# axe_tomb.net
KiCad netlist of a schematic drawn in EAGLE
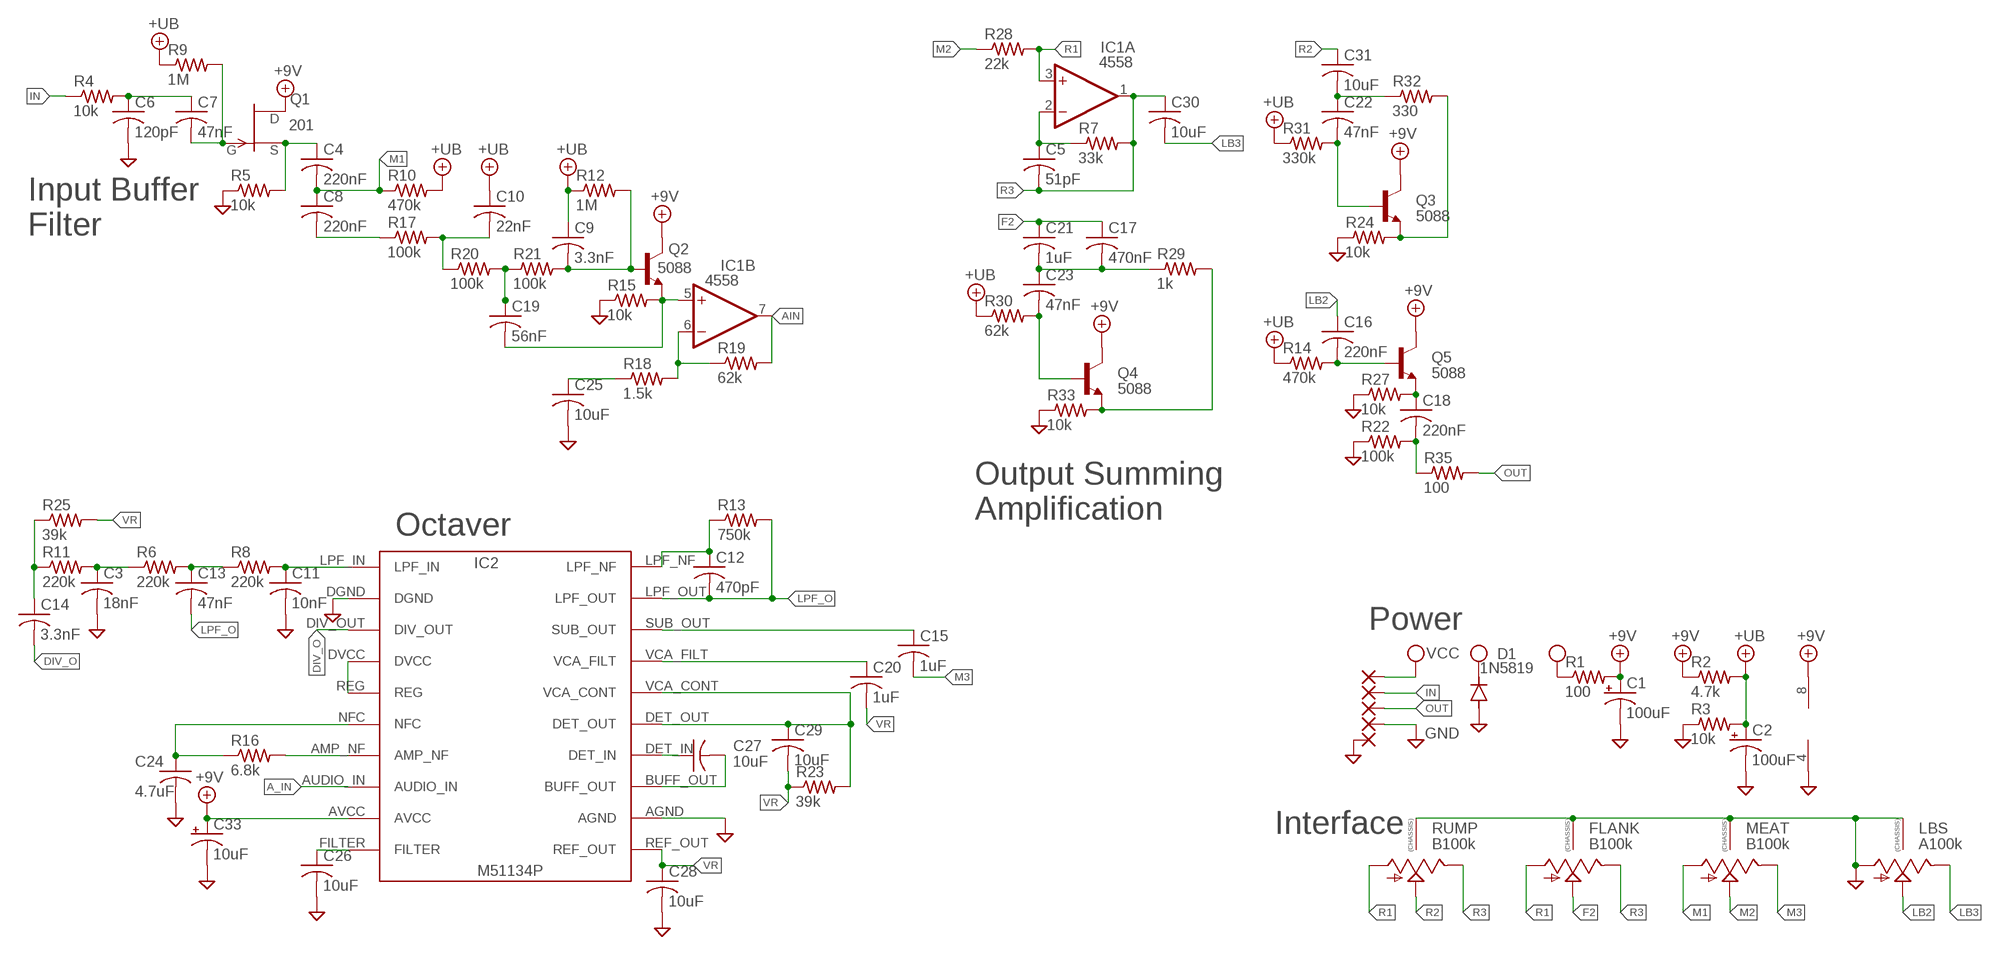
[diagram p0: schematic, sheet 1]

(export (version "E")
  (design (tool "Eeschema 10.0.6"))
  (components
    (comp (ref "C1")
      (value "100uF")
      (footprint "eagle-import:CPOL-RADIAL-2.5MM-6.5MM")
      (libsource (lib "eagle-import") (part "100UF-POLAR-RADIAL-2.5MM-25V-20%"))
    )
    (comp (ref "C2")
      (value "100uF")
      (footprint "eagle-import:CPOL-RADIAL-2.5MM-6.5MM")
      (libsource (lib "eagle-import") (part "100UF-POLAR-RADIAL-2.5MM-25V-20%"))
    )
    (comp (ref "C3")
      (value "18nF")
      (footprint "eagle-import:C0603")
      (libsource (lib "eagle-import") (part "C-USC0603"))
    )
    (comp (ref "C4")
      (value "220nF")
      (footprint "eagle-import:C0603")
      (libsource (lib "eagle-import") (part "C-USC0603"))
    )
    (comp (ref "C5")
      (value "51pF")
      (footprint "eagle-import:C0603")
      (libsource (lib "eagle-import") (part "C-USC0603"))
    )
    (comp (ref "C6")
      (value "120pF")
      (footprint "eagle-import:C0603")
      (libsource (lib "eagle-import") (part "C-USC0603"))
    )
    (comp (ref "C7")
      (value "47nF")
      (footprint "eagle-import:C0603")
      (libsource (lib "eagle-import") (part "C-USC0603"))
    )
    (comp (ref "C8")
      (value "220nF")
      (footprint "eagle-import:C0603")
      (libsource (lib "eagle-import") (part "C-USC0603"))
    )
    (comp (ref "C9")
      (value "3.3nF")
      (footprint "eagle-import:C0603")
      (libsource (lib "eagle-import") (part "C-USC0603"))
    )
    (comp (ref "C10")
      (value "22nF")
      (footprint "eagle-import:C0603")
      (libsource (lib "eagle-import") (part "C-USC0603"))
    )
    (comp (ref "C11")
      (value "10nF")
      (footprint "eagle-import:C0603")
      (libsource (lib "eagle-import") (part "C-USC0603"))
    )
    (comp (ref "C12")
      (value "470pF")
      (footprint "eagle-import:C0603")
      (libsource (lib "eagle-import") (part "C-USC0603"))
    )
    (comp (ref "C13")
      (value "47nF")
      (footprint "eagle-import:C0603")
      (libsource (lib "eagle-import") (part "C-USC0603"))
    )
    (comp (ref "C14")
      (value "3.3nF")
      (footprint "eagle-import:C0603")
      (libsource (lib "eagle-import") (part "C-USC0603"))
    )
    (comp (ref "C15")
      (value "1uF")
      (footprint "eagle-import:C0603")
      (libsource (lib "eagle-import") (part "C-USC0603"))
    )
    (comp (ref "C16")
      (value "220nF")
      (footprint "eagle-import:C0603")
      (libsource (lib "eagle-import") (part "C-USC0603"))
    )
    (comp (ref "C17")
      (value "470nF")
      (footprint "eagle-import:C0603")
      (libsource (lib "eagle-import") (part "C-USC0603"))
    )
    (comp (ref "C18")
      (value "220nF")
      (footprint "eagle-import:C0603")
      (libsource (lib "eagle-import") (part "C-USC0603"))
    )
    (comp (ref "C19")
      (value "56nF")
      (footprint "eagle-import:C0603")
      (libsource (lib "eagle-import") (part "C-USC0603"))
    )
    (comp (ref "C20")
      (value "1uF")
      (footprint "eagle-import:C0603")
      (libsource (lib "eagle-import") (part "C-USC0603"))
    )
    (comp (ref "C21")
      (value "1uF")
      (footprint "eagle-import:C0603")
      (libsource (lib "eagle-import") (part "C-USC0603"))
    )
    (comp (ref "C22")
      (value "47nF")
      (footprint "eagle-import:C0603")
      (libsource (lib "eagle-import") (part "C-USC0603"))
    )
    (comp (ref "C23")
      (value "47nF")
      (footprint "eagle-import:C0603")
      (libsource (lib "eagle-import") (part "C-USC0603"))
    )
    (comp (ref "C24")
      (value "4.7uF")
      (footprint "eagle-import:C1206")
      (libsource (lib "eagle-import") (part "C-USC1206"))
    )
    (comp (ref "C25")
      (value "10uF")
      (footprint "eagle-import:C1206")
      (libsource (lib "eagle-import") (part "C-USC1206"))
    )
    (comp (ref "C26")
      (value "10uF")
      (footprint "eagle-import:C1206")
      (libsource (lib "eagle-import") (part "C-USC1206"))
    )
    (comp (ref "C27")
      (value "10uF")
      (footprint "eagle-import:C1206")
      (libsource (lib "eagle-import") (part "C-USC1206"))
    )
    (comp (ref "C28")
      (value "10uF")
      (footprint "eagle-import:C1206")
      (libsource (lib "eagle-import") (part "C-USC1206"))
    )
    (comp (ref "C29")
      (value "10uF")
      (footprint "eagle-import:C1206")
      (libsource (lib "eagle-import") (part "C-USC1206"))
    )
    (comp (ref "C30")
      (value "10uF")
      (footprint "eagle-import:C1206")
      (libsource (lib "eagle-import") (part "C-USC1206"))
    )
    (comp (ref "C31")
      (value "10uF")
      (footprint "eagle-import:C1206")
      (libsource (lib "eagle-import") (part "C-USC1206"))
    )
    (comp (ref "C33")
      (value "10uF")
      (footprint "eagle-import:CAPMP3216X180N")
      (libsource (lib "eagle-import") (part "C-POL-USTANTALUM-1206(3216-METRIC)_"))
    )
    (comp (ref "D1")
      (value "1N5819")
      (footprint "eagle-import:SOD123")
      (libsource (lib "eagle-import") (part "DIODE-SOD123"))
    )
    (comp (ref "FLANK")
      (value "B100k")
      (footprint "eagle-import:9MM_SNAP-IN_POT")
      (libsource (lib "eagle-import") (part "9MM_SNAP-IN_POT_CHASSIS"))
    )
    (comp (ref "IC1")
      (value "4558")
      (footprint "eagle-import:SO08")
      (libsource (lib "eagle-import") (part "4558DLM"))
    )
    (comp (ref "IC2")
      (value "M51134P")
      (footprint "eagle-import:M51134P")
      (libsource (lib "eagle-import") (part "M51134P"))
    )
    (comp (ref "LBS")
      (value "A100k")
      (footprint "eagle-import:9MM_SNAP-IN_POT")
      (libsource (lib "eagle-import") (part "9MM_SNAP-IN_POT_CHASSIS"))
    )
    (comp (ref "MEAT")
      (value "B100k")
      (footprint "eagle-import:9MM_SNAP-IN_POT")
      (libsource (lib "eagle-import") (part "9MM_SNAP-IN_POT_CHASSIS"))
    )
    (comp (ref "PAD1")
      (value "1,6/0,8")
      (footprint "eagle-import:1,6_0,8")
      (libsource (lib "eagle-import") (part "1,6/0,8"))
    )
    (comp (ref "PAD2")
      (value "1,6/0,8")
      (footprint "eagle-import:1,6_0,8")
      (libsource (lib "eagle-import") (part "1,6/0,8"))
    )
    (comp (ref "PAD3")
      (value "1,6/0,8")
      (footprint "eagle-import:1,6_0,8")
      (libsource (lib "eagle-import") (part "1,6/0,8"))
    )
    (comp (ref "PAD4")
      (value "1,6/0,8")
      (footprint "eagle-import:1,6_0,8")
      (libsource (lib "eagle-import") (part "1,6/0,8"))
    )
    (comp (ref "PAD5")
      (value "1,6/0,8")
      (footprint "eagle-import:1,6_0,8")
      (libsource (lib "eagle-import") (part "1,6/0,8"))
    )
    (comp (ref "Q1")
      (value "201")
      (footprint "eagle-import:SOT23")
      (libsource (lib "eagle-import") (part "?20SST1"))
    )
    (comp (ref "Q2")
      (value "5088")
      (footprint "eagle-import:SOT23")
      (libsource (lib "eagle-import") (part "TRANSISTOR_NPNMMBT5088"))
    )
    (comp (ref "Q3")
      (value "5088")
      (footprint "eagle-import:SOT23")
      (libsource (lib "eagle-import") (part "TRANSISTOR_NPNMMBT5088"))
    )
    (comp (ref "Q4")
      (value "5088")
      (footprint "eagle-import:SOT23")
      (libsource (lib "eagle-import") (part "TRANSISTOR_NPNMMBT5088"))
    )
    (comp (ref "Q5")
      (value "5088")
      (footprint "eagle-import:SOT23")
      (libsource (lib "eagle-import") (part "TRANSISTOR_NPNMMBT5088"))
    )
    (comp (ref "R1")
      (value "100")
      (footprint "eagle-import:R0805")
      (libsource (lib "eagle-import") (part "adafruit_420_R-US_R0805"))
    )
    (comp (ref "R2")
      (value "4.7k")
      (footprint "eagle-import:R0603")
      (libsource (lib "eagle-import") (part "R-US_R0603"))
    )
    (comp (ref "R3")
      (value "10k")
      (footprint "eagle-import:R0603")
      (libsource (lib "eagle-import") (part "R-US_R0603"))
    )
    (comp (ref "R4")
      (value "10k")
      (footprint "eagle-import:R0603")
      (libsource (lib "eagle-import") (part "adafruit_420_R-US_R0603"))
    )
    (comp (ref "R5")
      (value "10k")
      (footprint "eagle-import:R0603")
      (libsource (lib "eagle-import") (part "adafruit_420_R-US_R0603"))
    )
    (comp (ref "R6")
      (value "220k")
      (footprint "eagle-import:R0603")
      (libsource (lib "eagle-import") (part "adafruit_420_R-US_R0603"))
    )
    (comp (ref "R7")
      (value "33k")
      (footprint "eagle-import:R0603")
      (libsource (lib "eagle-import") (part "adafruit_420_R-US_R0603"))
    )
    (comp (ref "R8")
      (value "220k")
      (footprint "eagle-import:R0603")
      (libsource (lib "eagle-import") (part "adafruit_420_R-US_R0603"))
    )
    (comp (ref "R9")
      (value "1M")
      (footprint "eagle-import:R0603")
      (libsource (lib "eagle-import") (part "adafruit_420_R-US_R0603"))
    )
    (comp (ref "R10")
      (value "470k")
      (footprint "eagle-import:R0603")
      (libsource (lib "eagle-import") (part "adafruit_420_R-US_R0603"))
    )
    (comp (ref "R11")
      (value "220k")
      (footprint "eagle-import:R0603")
      (libsource (lib "eagle-import") (part "adafruit_420_R-US_R0603"))
    )
    (comp (ref "R12")
      (value "1M")
      (footprint "eagle-import:R0603")
      (libsource (lib "eagle-import") (part "adafruit_420_R-US_R0603"))
    )
    (comp (ref "R13")
      (value "750k")
      (footprint "eagle-import:R0603")
      (libsource (lib "eagle-import") (part "adafruit_420_R-US_R0603"))
    )
    (comp (ref "R14")
      (value "470k")
      (footprint "eagle-import:R0603")
      (libsource (lib "eagle-import") (part "adafruit_420_R-US_R0603"))
    )
    (comp (ref "R15")
      (value "10k")
      (footprint "eagle-import:R0603")
      (libsource (lib "eagle-import") (part "adafruit_420_R-US_R0603"))
    )
    (comp (ref "R16")
      (value "6.8k")
      (footprint "eagle-import:R0603")
      (libsource (lib "eagle-import") (part "adafruit_420_R-US_R0603"))
    )
    (comp (ref "R17")
      (value "100k")
      (footprint "eagle-import:R0603")
      (libsource (lib "eagle-import") (part "adafruit_420_R-US_R0603"))
    )
    (comp (ref "R18")
      (value "1.5k")
      (footprint "eagle-import:R0603")
      (libsource (lib "eagle-import") (part "adafruit_420_R-US_R0603"))
    )
    (comp (ref "R19")
      (value "62k")
      (footprint "eagle-import:R0603")
      (libsource (lib "eagle-import") (part "adafruit_420_R-US_R0603"))
    )
    (comp (ref "R20")
      (value "100k")
      (footprint "eagle-import:R0603")
      (libsource (lib "eagle-import") (part "adafruit_420_R-US_R0603"))
    )
    (comp (ref "R21")
      (value "100k")
      (footprint "eagle-import:R0603")
      (libsource (lib "eagle-import") (part "adafruit_420_R-US_R0603"))
    )
    (comp (ref "R22")
      (value "100k")
      (footprint "eagle-import:R0603")
      (libsource (lib "eagle-import") (part "adafruit_420_R-US_R0603"))
    )
    (comp (ref "R23")
      (value "39k")
      (footprint "eagle-import:R0603")
      (libsource (lib "eagle-import") (part "adafruit_420_R-US_R0603"))
    )
    (comp (ref "R24")
      (value "10k")
      (footprint "eagle-import:R0603")
      (libsource (lib "eagle-import") (part "adafruit_420_R-US_R0603"))
    )
    (comp (ref "R25")
      (value "39k")
      (footprint "eagle-import:R0603")
      (libsource (lib "eagle-import") (part "adafruit_420_R-US_R0603"))
    )
    (comp (ref "R27")
      (value "10k")
      (footprint "eagle-import:R0603")
      (libsource (lib "eagle-import") (part "adafruit_420_R-US_R0603"))
    )
    (comp (ref "R28")
      (value "22k")
      (footprint "eagle-import:R0603")
      (libsource (lib "eagle-import") (part "adafruit_420_R-US_R0603"))
    )
    (comp (ref "R29")
      (value "1k")
      (footprint "eagle-import:R0603")
      (libsource (lib "eagle-import") (part "adafruit_420_R-US_R0603"))
    )
    (comp (ref "R30")
      (value "62k")
      (footprint "eagle-import:R0603")
      (libsource (lib "eagle-import") (part "adafruit_420_R-US_R0603"))
    )
    (comp (ref "R31")
      (value "330k")
      (footprint "eagle-import:R0603")
      (libsource (lib "eagle-import") (part "adafruit_420_R-US_R0603"))
    )
    (comp (ref "R32")
      (value "330")
      (footprint "eagle-import:R0603")
      (libsource (lib "eagle-import") (part "adafruit_420_R-US_R0603"))
    )
    (comp (ref "R33")
      (value "10k")
      (footprint "eagle-import:R0603")
      (libsource (lib "eagle-import") (part "adafruit_420_R-US_R0603"))
    )
    (comp (ref "R35")
      (value "100")
      (footprint "eagle-import:R0603")
      (libsource (lib "eagle-import") (part "adafruit_420_R-US_R0603"))
    )
    (comp (ref "RUMP")
      (value "B100k")
      (footprint "eagle-import:9MM_SNAP-IN_POT")
      (libsource (lib "eagle-import") (part "9MM_SNAP-IN_POT_CHASSIS"))
    )
  )
  (nets
    (net (code "1") (name "+9V") (class "Default")
      (node (ref "C1") (pin "1") (pinfunction "+_1") (pintype "passive"))
      (node (ref "C33") (pin "1") (pinfunction "+_1") (pintype "passive"))
      (node (ref "IC1") (pin "8") (pinfunction "V+_8") (pintype "power_in"))
      (node (ref "IC2") (pin "AVCC") (pinfunction "AVCC_AVCC") (pintype "bidirectional"))
      (node (ref "Q1") (pin "1") (pinfunction "D_1") (pintype "passive"))
      (node (ref "Q2") (pin "3") (pinfunction "C_3") (pintype "passive"))
      (node (ref "Q3") (pin "3") (pinfunction "C_3") (pintype "passive"))
      (node (ref "Q4") (pin "3") (pinfunction "C_3") (pintype "passive"))
      (node (ref "Q5") (pin "3") (pinfunction "C_3") (pintype "passive"))
      (node (ref "R1") (pin "2") (pinfunction "2_2") (pintype "passive"))
      (node (ref "R2") (pin "1") (pinfunction "1_1") (pintype "passive"))
    )
    (net (code "2") (name "+UB") (class "Default")
      (node (ref "C10") (pin "1") (pinfunction "1_1") (pintype "passive"))
      (node (ref "C2") (pin "1") (pinfunction "+_1") (pintype "passive"))
      (node (ref "C9") (pin "1") (pinfunction "1_1") (pintype "passive"))
      (node (ref "R10") (pin "2") (pinfunction "2_2") (pintype "passive"))
      (node (ref "R12") (pin "1") (pinfunction "1_1") (pintype "passive"))
      (node (ref "R14") (pin "1") (pinfunction "1_1") (pintype "passive"))
      (node (ref "R2") (pin "2") (pinfunction "2_2") (pintype "passive"))
      (node (ref "R3") (pin "2") (pinfunction "2_2") (pintype "passive"))
      (node (ref "R30") (pin "1") (pinfunction "1_1") (pintype "passive"))
      (node (ref "R31") (pin "1") (pinfunction "1_1") (pintype "passive"))
      (node (ref "R9") (pin "1") (pinfunction "1_1") (pintype "passive"))
    )
    (net (code "3") (name "AIN") (class "Default")
      (node (ref "IC1") (pin "7") (pinfunction "OUT_7") (pintype "output"))
      (node (ref "R19") (pin "2") (pinfunction "2_2") (pintype "passive"))
    )
    (net (code "4") (name "A_IN") (class "Default")
      (node (ref "IC2") (pin "AUDIO_IN") (pinfunction "AUDIO_IN_AUDIO_IN") (pintype "bidirectional"))
    )
    (net (code "5") (name "DIV_O") (class "Default")
      (node (ref "C14") (pin "2") (pinfunction "2_2") (pintype "passive"))
      (node (ref "IC2") (pin "DIV_OUT") (pinfunction "DIV_OUT_DIV_OUT") (pintype "bidirectional"))
    )
    (net (code "6") (name "F2") (class "Default")
      (node (ref "C17") (pin "1") (pinfunction "1_1") (pintype "passive"))
      (node (ref "C21") (pin "1") (pinfunction "1_1") (pintype "passive"))
      (node (ref "FLANK") (pin "2") (pinfunction "S_2") (pintype "passive"))
    )
    (net (code "7") (name "GND") (class "Default")
      (node (ref "C1") (pin "2") (pinfunction "-_2") (pintype "passive"))
      (node (ref "C11") (pin "2") (pinfunction "2_2") (pintype "passive"))
      (node (ref "C2") (pin "2") (pinfunction "-_2") (pintype "passive"))
      (node (ref "C24") (pin "2") (pinfunction "2_2") (pintype "passive"))
      (node (ref "C25") (pin "2") (pinfunction "2_2") (pintype "passive"))
      (node (ref "C26") (pin "2") (pinfunction "2_2") (pintype "passive"))
      (node (ref "C28") (pin "2") (pinfunction "2_2") (pintype "passive"))
      (node (ref "C3") (pin "2") (pinfunction "2_2") (pintype "passive"))
      (node (ref "C33") (pin "2") (pinfunction "-_2") (pintype "passive"))
      (node (ref "C6") (pin "2") (pinfunction "2_2") (pintype "passive"))
      (node (ref "D1") (pin "A") (pinfunction "A_A") (pintype "passive"))
      (node (ref "FLANK") (pin "CHASSIS1") (pinfunction "P$1_CHASSIS1") (pintype "passive"))
      (node (ref "FLANK") (pin "CHASSIS2") (pinfunction "P$1_CHASSIS2") (pintype "passive"))
      (node (ref "IC1") (pin "4") (pinfunction "V-_4") (pintype "power_in"))
      (node (ref "IC2") (pin "AGND") (pinfunction "AGND_AGND") (pintype "bidirectional"))
      (node (ref "IC2") (pin "DGND") (pinfunction "DGND_DGND") (pintype "bidirectional"))
      (node (ref "LBS") (pin "1") (pinfunction "A_1") (pintype "passive"))
      (node (ref "LBS") (pin "CHASSIS1") (pinfunction "P$1_CHASSIS1") (pintype "passive"))
      (node (ref "LBS") (pin "CHASSIS2") (pinfunction "P$1_CHASSIS2") (pintype "passive"))
      (node (ref "MEAT") (pin "CHASSIS1") (pinfunction "P$1_CHASSIS1") (pintype "passive"))
      (node (ref "MEAT") (pin "CHASSIS2") (pinfunction "P$1_CHASSIS2") (pintype "passive"))
      (node (ref "PAD4") (pin "1") (pinfunction "P_1") (pintype "passive"))
      (node (ref "PAD5") (pin "1") (pinfunction "P_1") (pintype "passive"))
      (node (ref "R15") (pin "1") (pinfunction "1_1") (pintype "passive"))
      (node (ref "R22") (pin "1") (pinfunction "1_1") (pintype "passive"))
      (node (ref "R24") (pin "1") (pinfunction "1_1") (pintype "passive"))
      (node (ref "R27") (pin "1") (pinfunction "1_1") (pintype "passive"))
      (node (ref "R3") (pin "1") (pinfunction "1_1") (pintype "passive"))
      (node (ref "R33") (pin "1") (pinfunction "1_1") (pintype "passive"))
      (node (ref "R5") (pin "1") (pinfunction "1_1") (pintype "passive"))
      (node (ref "RUMP") (pin "CHASSIS1") (pinfunction "P$1_CHASSIS1") (pintype "passive"))
      (node (ref "RUMP") (pin "CHASSIS2") (pinfunction "P$1_CHASSIS2") (pintype "passive"))
    )
    (net (code "8") (name "IN") (class "Default")
      (node (ref "PAD2") (pin "1") (pinfunction "P_1") (pintype "passive"))
      (node (ref "R4") (pin "1") (pinfunction "1_1") (pintype "passive"))
    )
    (net (code "9") (name "LB2") (class "Default")
      (node (ref "C16") (pin "1") (pinfunction "1_1") (pintype "passive"))
      (node (ref "LBS") (pin "2") (pinfunction "S_2") (pintype "passive"))
    )
    (net (code "10") (name "LB3") (class "Default")
      (node (ref "C30") (pin "2") (pinfunction "2_2") (pintype "passive"))
      (node (ref "LBS") (pin "3") (pinfunction "E_3") (pintype "passive"))
    )
    (net (code "11") (name "LPF_O") (class "Default")
      (node (ref "C12") (pin "2") (pinfunction "2_2") (pintype "passive"))
      (node (ref "C13") (pin "2") (pinfunction "2_2") (pintype "passive"))
      (node (ref "IC2") (pin "LPF_OUT") (pinfunction "LPF_OUT_LPF_OUT") (pintype "bidirectional"))
      (node (ref "R13") (pin "2") (pinfunction "2_2") (pintype "passive"))
    )
    (net (code "12") (name "M1") (class "Default")
      (node (ref "C4") (pin "2") (pinfunction "2_2") (pintype "passive"))
      (node (ref "C8") (pin "1") (pinfunction "1_1") (pintype "passive"))
      (node (ref "MEAT") (pin "1") (pinfunction "A_1") (pintype "passive"))
      (node (ref "R10") (pin "1") (pinfunction "1_1") (pintype "passive"))
    )
    (net (code "13") (name "M2") (class "Default")
      (node (ref "MEAT") (pin "2") (pinfunction "S_2") (pintype "passive"))
      (node (ref "R28") (pin "1") (pinfunction "1_1") (pintype "passive"))
    )
    (net (code "14") (name "M3") (class "Default")
      (node (ref "C15") (pin "2") (pinfunction "2_2") (pintype "passive"))
      (node (ref "MEAT") (pin "3") (pinfunction "E_3") (pintype "passive"))
    )
    (net (code "15") (name "Net-(C3-Pad1)") (class "Default")
      (node (ref "C3") (pin "1") (pinfunction "1_1") (pintype "passive"))
      (node (ref "R11") (pin "2") (pinfunction "2_2") (pintype "passive"))
      (node (ref "R6") (pin "1") (pinfunction "1_1") (pintype "passive"))
    )
    (net (code "16") (name "Net-(C6-Pad1)") (class "Default")
      (node (ref "C6") (pin "1") (pinfunction "1_1") (pintype "passive"))
      (node (ref "C7") (pin "1") (pinfunction "1_1") (pintype "passive"))
      (node (ref "R4") (pin "2") (pinfunction "2_2") (pintype "passive"))
    )
    (net (code "17") (name "Net-(C8-Pad2)") (class "Default")
      (node (ref "C8") (pin "2") (pinfunction "2_2") (pintype "passive"))
      (node (ref "R17") (pin "1") (pinfunction "1_1") (pintype "passive"))
    )
    (net (code "18") (name "Net-(C10-Pad2)") (class "Default")
      (node (ref "C10") (pin "2") (pinfunction "2_2") (pintype "passive"))
      (node (ref "R17") (pin "2") (pinfunction "2_2") (pintype "passive"))
      (node (ref "R20") (pin "1") (pinfunction "1_1") (pintype "passive"))
    )
    (net (code "19") (name "Net-(C11-Pad1)") (class "Default")
      (node (ref "C11") (pin "1") (pinfunction "1_1") (pintype "passive"))
      (node (ref "IC2") (pin "LPF_IN") (pinfunction "LPF_IN_LPF_IN") (pintype "bidirectional"))
      (node (ref "R8") (pin "2") (pinfunction "2_2") (pintype "passive"))
    )
    (net (code "20") (name "Net-(C12-Pad1)") (class "Default")
      (node (ref "C12") (pin "1") (pinfunction "1_1") (pintype "passive"))
      (node (ref "IC2") (pin "LPF_NF") (pinfunction "LPF_NF_LPF_NF") (pintype "bidirectional"))
      (node (ref "R13") (pin "1") (pinfunction "1_1") (pintype "passive"))
    )
    (net (code "21") (name "Net-(C13-Pad1)") (class "Default")
      (node (ref "C13") (pin "1") (pinfunction "1_1") (pintype "passive"))
      (node (ref "R6") (pin "2") (pinfunction "2_2") (pintype "passive"))
      (node (ref "R8") (pin "1") (pinfunction "1_1") (pintype "passive"))
    )
    (net (code "22") (name "Net-(C14-Pad1)") (class "Default")
      (node (ref "C14") (pin "1") (pinfunction "1_1") (pintype "passive"))
      (node (ref "R11") (pin "1") (pinfunction "1_1") (pintype "passive"))
      (node (ref "R25") (pin "1") (pinfunction "1_1") (pintype "passive"))
    )
    (net (code "23") (name "Net-(C15-Pad1)") (class "Default")
      (node (ref "C15") (pin "1") (pinfunction "1_1") (pintype "passive"))
      (node (ref "IC2") (pin "SUB_OUT") (pinfunction "SUB_OUT_SUB_OUT") (pintype "bidirectional"))
    )
    (net (code "24") (name "Net-(C17-Pad2)") (class "Default")
      (node (ref "C17") (pin "2") (pinfunction "2_2") (pintype "passive"))
      (node (ref "C21") (pin "2") (pinfunction "2_2") (pintype "passive"))
      (node (ref "C23") (pin "1") (pinfunction "1_1") (pintype "passive"))
      (node (ref "R29") (pin "1") (pinfunction "1_1") (pintype "passive"))
    )
    (net (code "25") (name "Net-(C18-Pad2)") (class "Default")
      (node (ref "C18") (pin "2") (pinfunction "2_2") (pintype "passive"))
      (node (ref "R22") (pin "2") (pinfunction "2_2") (pintype "passive"))
      (node (ref "R35") (pin "1") (pinfunction "1_1") (pintype "passive"))
    )
    (net (code "26") (name "Net-(C19-Pad1)") (class "Default")
      (node (ref "C19") (pin "1") (pinfunction "1_1") (pintype "passive"))
      (node (ref "R20") (pin "2") (pinfunction "2_2") (pintype "passive"))
      (node (ref "R21") (pin "1") (pinfunction "1_1") (pintype "passive"))
    )
    (net (code "27") (name "Net-(C20-Pad1)") (class "Default")
      (node (ref "C20") (pin "1") (pinfunction "1_1") (pintype "passive"))
      (node (ref "IC2") (pin "VCA_FILT") (pinfunction "VCA_FILT_VCA_FILT") (pintype "bidirectional"))
    )
    (net (code "28") (name "Net-(C22-Pad1)") (class "Default")
      (node (ref "C22") (pin "1") (pinfunction "1_1") (pintype "passive"))
      (node (ref "C31") (pin "2") (pinfunction "2_2") (pintype "passive"))
      (node (ref "R32") (pin "1") (pinfunction "1_1") (pintype "passive"))
    )
    (net (code "29") (name "Net-(C24-Pad1)") (class "Default")
      (node (ref "C24") (pin "1") (pinfunction "1_1") (pintype "passive"))
      (node (ref "IC2") (pin "NFC") (pinfunction "NFC_NFC") (pintype "bidirectional"))
      (node (ref "R16") (pin "1") (pinfunction "1_1") (pintype "passive"))
    )
    (net (code "30") (name "Net-(C25-Pad1)") (class "Default")
      (node (ref "C25") (pin "1") (pinfunction "1_1") (pintype "passive"))
      (node (ref "R18") (pin "1") (pinfunction "1_1") (pintype "passive"))
    )
    (net (code "31") (name "Net-(C26-Pad1)") (class "Default")
      (node (ref "C26") (pin "1") (pinfunction "1_1") (pintype "passive"))
      (node (ref "IC2") (pin "FILTER") (pinfunction "FILTER_FILTER") (pintype "bidirectional"))
    )
    (net (code "32") (name "Net-(C27-Pad1)") (class "Default")
      (node (ref "C27") (pin "1") (pinfunction "1_1") (pintype "passive"))
      (node (ref "IC2") (pin "DET_IN") (pinfunction "DET_IN_DET_IN") (pintype "bidirectional"))
    )
    (net (code "33") (name "Net-(C27-Pad2)") (class "Default")
      (node (ref "C27") (pin "2") (pinfunction "2_2") (pintype "passive"))
      (node (ref "IC2") (pin "BUFF_OUT") (pinfunction "BUFF_OUT_BUFF_OUT") (pintype "bidirectional"))
    )
    (net (code "34") (name "Net-(C29-Pad1)") (class "Default")
      (node (ref "C29") (pin "1") (pinfunction "1_1") (pintype "passive"))
      (node (ref "IC2") (pin "DET_OUT") (pinfunction "DET_OUT_DET_OUT") (pintype "bidirectional"))
      (node (ref "IC2") (pin "VCA_CONT") (pinfunction "VCA_CONT_VCA_CONT") (pintype "bidirectional"))
      (node (ref "R23") (pin "2") (pinfunction "2_2") (pintype "passive"))
    )
    (net (code "35") (name "Net-(IC1A--IN)") (class "Default")
      (node (ref "C5") (pin "1") (pinfunction "1_1") (pintype "passive"))
      (node (ref "IC1") (pin "2") (pinfunction "-IN_2") (pintype "input"))
      (node (ref "R7") (pin "1") (pinfunction "1_1") (pintype "passive"))
    )
    (net (code "36") (name "Net-(IC1B-+IN)") (class "Default")
      (node (ref "C19") (pin "2") (pinfunction "2_2") (pintype "passive"))
      (node (ref "IC1") (pin "5") (pinfunction "+IN_5") (pintype "input"))
      (node (ref "Q2") (pin "2") (pinfunction "E_2") (pintype "passive"))
      (node (ref "R15") (pin "2") (pinfunction "2_2") (pintype "passive"))
    )
    (net (code "37") (name "Net-(IC1B--IN)") (class "Default")
      (node (ref "IC1") (pin "6") (pinfunction "-IN_6") (pintype "input"))
      (node (ref "R18") (pin "2") (pinfunction "2_2") (pintype "passive"))
      (node (ref "R19") (pin "1") (pinfunction "1_1") (pintype "passive"))
    )
    (net (code "38") (name "Net-(IC2-PadAMP_NF)") (class "Default")
      (node (ref "IC2") (pin "AMP_NF") (pinfunction "AMP_NF_AMP_NF") (pintype "bidirectional"))
      (node (ref "R16") (pin "2") (pinfunction "2_2") (pintype "passive"))
    )
    (net (code "39") (name "Net-(IC2-PadDVCC)") (class "Default")
      (node (ref "IC2") (pin "DVCC") (pinfunction "DVCC_DVCC") (pintype "bidirectional"))
      (node (ref "IC2") (pin "REG") (pinfunction "REG_REG") (pintype "bidirectional"))
    )
    (net (code "40") (name "Net-(Q1-G)") (class "Default")
      (node (ref "C7") (pin "2") (pinfunction "2_2") (pintype "passive"))
      (node (ref "Q1") (pin "3") (pinfunction "G_3") (pintype "passive"))
      (node (ref "R9") (pin "2") (pinfunction "2_2") (pintype "passive"))
    )
    (net (code "41") (name "Net-(Q1-S)") (class "Default")
      (node (ref "C4") (pin "1") (pinfunction "1_1") (pintype "passive"))
      (node (ref "Q1") (pin "2") (pinfunction "S_2") (pintype "passive"))
      (node (ref "R5") (pin "2") (pinfunction "2_2") (pintype "passive"))
    )
    (net (code "42") (name "Net-(Q2-B)") (class "Default")
      (node (ref "C9") (pin "2") (pinfunction "2_2") (pintype "passive"))
      (node (ref "Q2") (pin "1") (pinfunction "B_1") (pintype "passive"))
      (node (ref "R12") (pin "2") (pinfunction "2_2") (pintype "passive"))
      (node (ref "R21") (pin "2") (pinfunction "2_2") (pintype "passive"))
    )
    (net (code "43") (name "Net-(Q3-B)") (class "Default")
      (node (ref "C22") (pin "2") (pinfunction "2_2") (pintype "passive"))
      (node (ref "Q3") (pin "1") (pinfunction "B_1") (pintype "passive"))
      (node (ref "R31") (pin "2") (pinfunction "2_2") (pintype "passive"))
    )
    (net (code "44") (name "Net-(Q3-E)") (class "Default")
      (node (ref "Q3") (pin "2") (pinfunction "E_2") (pintype "passive"))
      (node (ref "R24") (pin "2") (pinfunction "2_2") (pintype "passive"))
      (node (ref "R32") (pin "2") (pinfunction "2_2") (pintype "passive"))
    )
    (net (code "45") (name "Net-(Q4-B)") (class "Default")
      (node (ref "C23") (pin "2") (pinfunction "2_2") (pintype "passive"))
      (node (ref "Q4") (pin "1") (pinfunction "B_1") (pintype "passive"))
      (node (ref "R30") (pin "2") (pinfunction "2_2") (pintype "passive"))
    )
    (net (code "46") (name "Net-(Q4-E)") (class "Default")
      (node (ref "Q4") (pin "2") (pinfunction "E_2") (pintype "passive"))
      (node (ref "R29") (pin "2") (pinfunction "2_2") (pintype "passive"))
      (node (ref "R33") (pin "2") (pinfunction "2_2") (pintype "passive"))
    )
    (net (code "47") (name "Net-(Q5-B)") (class "Default")
      (node (ref "C16") (pin "2") (pinfunction "2_2") (pintype "passive"))
      (node (ref "Q5") (pin "1") (pinfunction "B_1") (pintype "passive"))
      (node (ref "R14") (pin "2") (pinfunction "2_2") (pintype "passive"))
    )
    (net (code "48") (name "Net-(Q5-E)") (class "Default")
      (node (ref "C18") (pin "1") (pinfunction "1_1") (pintype "passive"))
      (node (ref "Q5") (pin "2") (pinfunction "E_2") (pintype "passive"))
      (node (ref "R27") (pin "2") (pinfunction "2_2") (pintype "passive"))
    )
    (net (code "49") (name "OUT") (class "Default")
      (node (ref "PAD3") (pin "1") (pinfunction "P_1") (pintype "passive"))
      (node (ref "R35") (pin "2") (pinfunction "2_2") (pintype "passive"))
    )
    (net (code "50") (name "R1") (class "Default")
      (node (ref "FLANK") (pin "1") (pinfunction "A_1") (pintype "passive"))
      (node (ref "IC1") (pin "3") (pinfunction "+IN_3") (pintype "input"))
      (node (ref "R28") (pin "2") (pinfunction "2_2") (pintype "passive"))
      (node (ref "RUMP") (pin "1") (pinfunction "A_1") (pintype "passive"))
    )
    (net (code "51") (name "R2") (class "Default")
      (node (ref "C31") (pin "1") (pinfunction "1_1") (pintype "passive"))
      (node (ref "RUMP") (pin "2") (pinfunction "S_2") (pintype "passive"))
    )
    (net (code "52") (name "R3") (class "Default")
      (node (ref "C30") (pin "1") (pinfunction "1_1") (pintype "passive"))
      (node (ref "C5") (pin "2") (pinfunction "2_2") (pintype "passive"))
      (node (ref "FLANK") (pin "3") (pinfunction "E_3") (pintype "passive"))
      (node (ref "IC1") (pin "1") (pinfunction "OUT_1") (pintype "output"))
      (node (ref "R7") (pin "2") (pinfunction "2_2") (pintype "passive"))
      (node (ref "RUMP") (pin "3") (pinfunction "E_3") (pintype "passive"))
    )
    (net (code "53") (name "VCC") (class "Default")
      (node (ref "D1") (pin "C") (pinfunction "C_C") (pintype "passive"))
      (node (ref "PAD1") (pin "1") (pinfunction "P_1") (pintype "passive"))
      (node (ref "R1") (pin "1") (pinfunction "1_1") (pintype "passive"))
    )
    (net (code "54") (name "VR") (class "Default")
      (node (ref "C20") (pin "2") (pinfunction "2_2") (pintype "passive"))
      (node (ref "C28") (pin "1") (pinfunction "1_1") (pintype "passive"))
      (node (ref "C29") (pin "2") (pinfunction "2_2") (pintype "passive"))
      (node (ref "IC2") (pin "REF_OUT") (pinfunction "REF_OUT_REF_OUT") (pintype "bidirectional"))
      (node (ref "R23") (pin "1") (pinfunction "1_1") (pintype "passive"))
      (node (ref "R25") (pin "2") (pinfunction "2_2") (pintype "passive"))
    )
  )
)
